# power-supply.net
KiCad netlist of a schematic drawn in Altium Designer
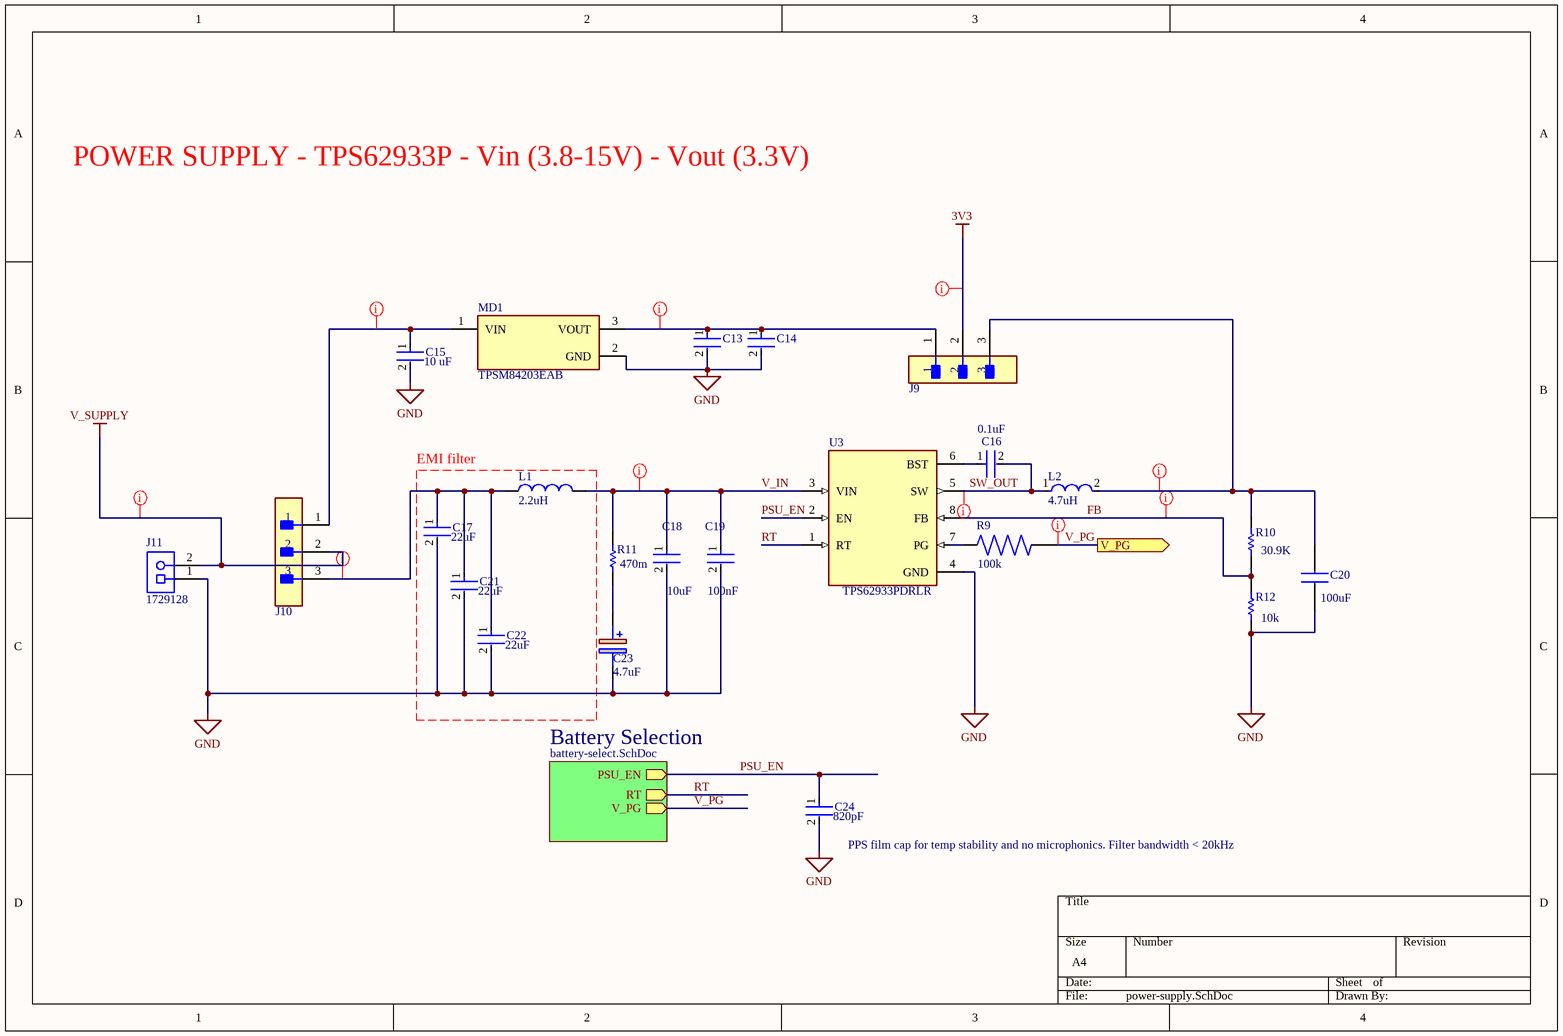
[diagram p0: power-supply.SchDoc]

(export (version "E")
  (design (tool "Eeschema 10.0.6"))
  (components
    (comp (ref "C13")
      (value "~")
      (footprint "FP-C3216-160-0_2-MFG")
      (description "Multilayer Ceramic Capacitors 47uF ±20% 25V X5R SMD 1206")
      (fields (field (name "VOLTAGE") "25V") (field (name "TOLERANCE") "20%"))
      (libsource (lib "FLoRa0.0") (part "11868f565c42a9108669ba33697ecf6"))
    )
    (comp (ref "C14")
      (value "~")
      (footprint "FP-C3216-160-0_2-MFG")
      (description "Multilayer Ceramic Capacitors 47uF ±20% 25V X5R SMD 1206")
      (fields (field (name "VOLTAGE") "25V") (field (name "TOLERANCE") "20%"))
      (libsource (lib "FLoRa0.0") (part "11868f565c42a9108669ba33697ecf6"))
    )
    (comp (ref "C15")
      (value "10 uF")
      (footprint "FP-GRT31C-0_2-IPC_A")
      (description "Multi-Layer Ceramic Capacitor 10uF 50V X5R ±10% 1206 Emboss T/R")
      (fields (field (name "TOLERANCE") "10%"))
      (libsource (lib "Altium Content Vault") (part "02cd4be3c70576c341d710602a673aa"))
    )
    (comp (ref "C16")
      (value "0.1uF")
      (footprint "FP-C0603C104Z4VACTU-MFG")
      (description "CAP CER 0.1UF 16V Y5V 0603")
      (fields (field (name "TOLERANCE") "80%"))
      (libsource (lib "Altium Content Vault") (part "b4654b650e69147ec39a6b967a45e02"))
    )
    (comp (ref "C17")
      (value "22uF")
      (footprint "FP-GRM32-MFG")
      (description "CAP CER 22UF 25V X5R 1210")
      (fields
        (field (name "TOLERANCE") "10%")
        (field (name "MANUFACTURER") "Murata Electronics North America")
      )
      (libsource (lib "Altium Content Vault") (part "11868f565c42a9108669ba33697ecf6"))
    )
    (comp (ref "C18")
      (value "10uF")
      (footprint "FP-GRM21B-0_15-IPC_A")
      (description "Chip Multilayer Ceramic Capacitors for General Purpose, 0805, 10uF, X5R, 15%, 20%, 25V")
      (fields (field (name "TOLERANCE") "20%"))
      (libsource (lib "Altium Content Vault") (part "b4654b650e69147ec39a6b967a45e02"))
    )
    (comp (ref "C19")
      (value "100nF")
      (footprint "FP-0603-L_1_6_0_15-W_0_81-MFG")
      (description "General Purpose Ceramic Capacitor, 0603, 100nF, 10%, X7R, 15%, 25V")
      (fields (field (name "VOLTAGE") "25V") (field (name "TOLERANCE") "10%"))
      (libsource (lib "Altium Content Vault") (part "02cd4be3c70576c341d710602a673aa"))
    )
    (comp (ref "C20")
      (value "100uF")
      (footprint "CAPC3225X270N")
      (fields
        (field (name "MOUSER PART NUMBER") "81-GRM32EC80J107ME0L")
        (field (name "MANUFACTURER_PART_NUMBER") "GRM32EC80J107ME20L")
      )
      (libsource (lib "GRM32EC80J107ME20L") (part "GRM32EC80J107ME20L"))
    )
    (comp (ref "C21")
      (value "22uF")
      (footprint "FP-GRM32-MFG")
      (description "CAP CER 22UF 25V X5R 1210")
      (fields
        (field (name "TOLERANCE") "10%")
        (field (name "MANUFACTURER") "Murata Electronics North America")
      )
      (libsource (lib "Altium Content Vault") (part "11868f565c42a9108669ba33697ecf6"))
    )
    (comp (ref "C22")
      (value "22uF")
      (footprint "FP-GRM32-MFG")
      (description "CAP CER 22UF 25V X5R 1210")
      (fields
        (field (name "TOLERANCE") "10%")
        (field (name "MANUFACTURER") "Murata Electronics North America")
      )
      (libsource (lib "Altium Content Vault") (part "11868f565c42a9108669ba33697ecf6"))
    )
    (comp (ref "C23")
      (value "4.7uF")
      (footprint "CAPPM3528X120N")
      (description "Cap Tant Solid 4.7uF 35V B CASE 10% (3.5 X 2.8 X 1.9mm) Inward L SMD 3528-21 0.7 Ohm 125C T/R")
      (fields
        (field (name "MOUSER PART NUMBER") "581-TPSB475K035R0700")
        (field (name "MANUFACTURER_PART_NUMBER") "TPSB475K035R0700")
      )
      (libsource (lib "TPSB475K035R0700") (part "TPSB475K035R0700"))
    )
    (comp (ref "C24")
      (value "ECH-U1H821JX5")
      (footprint "FP-ECHUJ1-MFG")
      (description "CAP FILM 820PF 5% 50VDC 0805")
      (fields
        (field (name "TOLERANCE") "5%")
        (field (name "CAPACITANCE") "820pF")
        (field (name "VOLTAGE") "50V")
      )
      (libsource (lib "Altium Content Vault") (part "b4654b650e69147ec39a6b967a45e02"))
    )
    (comp (ref "J9")
      (value "PREC003SAAN-RC")
      (footprint "FP-PREC003SAAN-RC-MFG")
      (description "PREC003SAAN-RC Conn Header Vert 3POS 2.54MM")
      (libsource (lib "Altium Content Vault") (part "0d3f023dd272f625e17a2be33dea85f"))
    )
    (comp (ref "J10")
      (value "3POS_MALECONN-2.54mm")
      (footprint "FLoRa0.02:SIP3-100mil")
      (description "Vertical male 3 position connector 2.54mm pitch")
      (libsource (lib "FLoRa0.0") (part "3POS_MALECONN-2.54mm"))
    )
    (comp (ref "J11")
      (value "1729128")
      (footprint "FLoRa0.02:PHOE-1729128-2_V")
      (description "PCB Terminal Block, 13.5 A, 400 V, 2-Pin THD, RoHS, Bulk")
      (fields (field (name "MANUFACTURER") "Phoenix Contact"))
      (libsource (lib "FLoRa0.0") (part "CMP-2000-05815-1"))
    )
    (comp (ref "L1")
      (value "2.2uH")
      (footprint "WE-PMCI_1210_L3.2W2.5H1.2")
      (description "74479299222 General Purpose Inductor, 2.2uH, 15%, 1 Element, Iron Alloy-Core, SMD, 1210")
      (fields (field (name "TOLERANCE") "20%"))
      (libsource (lib "Altium Content Vault") (part "Inductor - 1"))
    )
    (comp (ref "L2")
      (value "4.7uH")
      (footprint "FP-IHLP-3232DZ-FP_2_413x5-MFG")
      (description "Commercial Inductors, Low DCR Series 4.7uH 8A 22.6mΩ 20%")
      (fields (field (name "TOLERANCE") "20%"))
      (libsource (lib "Altium Content Vault") (part "725321dda6339637d4d059423bc1c3c"))
    )
    (comp (ref "MD1")
      (value "TPSM84203EAB")
      (footprint "FLoRa0.02:FP-EAB0003A-MFG")
      (description "Switching Regulator, Current-mode, 1.5A, 510kHz Switching Freq-Max, Hybrid")
      (fields (field (name "MANUFACTURER") "Texas Instruments"))
      (libsource (lib "FLoRa0.0") (part "TPS_EVAL_BOARD"))
    )
    (comp (ref "R9")
      (value "100k")
      (footprint "RESC1508X50N")
      (fields (field (name "MF") "Vishay") (field (name "MP") "CRCW0603100KFKEA"))
      (libsource (lib "CRCW0603100KFKEA") (part "CRCW0603100KFKEA"))
    )
    (comp (ref "R10")
      (value "30.9K")
      (footprint "RESC1608X55X25NL10T15")
      (description "Rfbt")
      (fields (field (name "MANUFACTURER") "Yageo") (field (name "PART NUMBER") "RC0603FR-0730K9L"))
      (libsource (lib "Altium Content Vault") (part "RES"))
    )
    (comp (ref "R11")
      (value "470m")
      (footprint "RESC2013X70X40NL20T20")
      (fields (field (name "MANUFACTURER") "Panasonic") (field (name "PART NUMBER") "ERJ-6RQFR47V"))
      (libsource (lib "Altium Content Vault") (part "RES"))
    )
    (comp (ref "R12")
      (value "10k")
      (footprint "RESC1609X50X30NL8T20")
      (fields (field (name "MANUFACTURER") "Vishay Semiconductor"))
      (libsource (lib "Altium Content Vault") (part "RES-2"))
    )
    (comp (ref "U3")
      (value "TPS62933PDRLR")
      (footprint "SOFL50P160X60-8S")
      (libsource (lib "TPS62933PDRLR") (part "TPS62933PDRLR"))
    )
  )
  (nets
    (net (code "1") (name "/FB") (class "Default")
      (node (ref "R10") (pin "1") (pinfunction "1_1") (pintype "passive"))
      (node (ref "R12") (pin "2") (pinfunction "2_2") (pintype "passive"))
      (node (ref "U3") (pin "8") (pinfunction "FB_8") (pintype "input"))
    )
    (net (code "2") (name "/PSU_EN") (class "Default")
      (node (ref "C24") (pin "1") (pinfunction "1_1") (pintype "passive"))
      (node (ref "U3") (pin "2") (pinfunction "EN_2") (pintype "input"))
    )
    (net (code "3") (name "/RT") (class "Default")
      (node (ref "U3") (pin "1") (pinfunction "RT_1") (pintype "input"))
    )
    (net (code "4") (name "/SW_OUT") (class "Default")
      (node (ref "C16") (pin "2") (pinfunction "2_2") (pintype "passive"))
      (node (ref "L2") (pin "1") (pinfunction "1_1") (pintype "passive"))
      (node (ref "U3") (pin "5") (pinfunction "SW_5") (pintype "output"))
    )
    (net (code "5") (name "/V_IN") (class "Default")
      (node (ref "C18") (pin "1") (pinfunction "1_1") (pintype "passive"))
      (node (ref "C19") (pin "1") (pinfunction "1_1") (pintype "passive"))
      (node (ref "L1") (pin "2") (pinfunction "2_2") (pintype "passive"))
      (node (ref "R11") (pin "2") (pinfunction "2_2") (pintype "passive"))
      (node (ref "U3") (pin "3") (pinfunction "VIN_3") (pintype "input"))
    )
    (net (code "6") (name "/V_PG") (class "Default")
      (node (ref "R9") (pin "2") (pinfunction "2_2") (pintype "passive"))
    )
    (net (code "7") (name "3V3") (class "Default")
      (node (ref "J9") (pin "2") (pinfunction "2_2") (pintype "passive"))
    )
    (net (code "8") (name "GND") (class "Default")
      (node (ref "C13") (pin "2") (pinfunction "2_2") (pintype "passive"))
      (node (ref "C14") (pin "2") (pinfunction "2_2") (pintype "passive"))
      (node (ref "C15") (pin "2") (pinfunction "2_2") (pintype "passive"))
      (node (ref "C17") (pin "2") (pinfunction "2_2") (pintype "passive"))
      (node (ref "C18") (pin "2") (pinfunction "2_2") (pintype "passive"))
      (node (ref "C19") (pin "2") (pinfunction "2_2") (pintype "passive"))
      (node (ref "C20") (pin "1") (pinfunction "1_1") (pintype "passive"))
      (node (ref "C21") (pin "2") (pinfunction "2_2") (pintype "passive"))
      (node (ref "C22") (pin "2") (pinfunction "2_2") (pintype "passive"))
      (node (ref "C23") (pin "2") (pinfunction "-_2") (pintype "passive"))
      (node (ref "C24") (pin "2") (pinfunction "2_2") (pintype "passive"))
      (node (ref "J11") (pin "1") (pinfunction "1_1") (pintype "passive"))
      (node (ref "MD1") (pin "2") (pinfunction "GND_2") (pintype "power_in"))
      (node (ref "R12") (pin "1") (pinfunction "1_1") (pintype "passive"))
      (node (ref "U3") (pin "4") (pinfunction "GND_4") (pintype "power_in"))
    )
    (net (code "9") (name "Net-(C17-Pad1)") (class "Default")
      (node (ref "C17") (pin "1") (pinfunction "1_1") (pintype "passive"))
      (node (ref "C21") (pin "1") (pinfunction "1_1") (pintype "passive"))
      (node (ref "C22") (pin "1") (pinfunction "1_1") (pintype "passive"))
      (node (ref "J10") (pin "3") (pinfunction "3_3") (pintype "passive"))
      (node (ref "L1") (pin "1") (pinfunction "1_1") (pintype "passive"))
    )
    (net (code "10") (name "Net-(C20-Pad2)") (class "Default")
      (node (ref "C20") (pin "2") (pinfunction "2_2") (pintype "passive"))
      (node (ref "J9") (pin "3") (pinfunction "3_3") (pintype "passive"))
      (node (ref "L2") (pin "2") (pinfunction "2_2") (pintype "passive"))
      (node (ref "R10") (pin "2") (pinfunction "2_2") (pintype "passive"))
    )
    (net (code "11") (name "Net-(C23-+)") (class "Default")
      (node (ref "C23") (pin "1") (pinfunction "+_1") (pintype "passive"))
      (node (ref "R11") (pin "1") (pinfunction "1_1") (pintype "passive"))
    )
    (net (code "12") (name "Net-(MD1-VIN)") (class "Default")
      (node (ref "C15") (pin "1") (pinfunction "1_1") (pintype "passive"))
      (node (ref "J10") (pin "1") (pinfunction "1_1") (pintype "passive"))
      (node (ref "MD1") (pin "1") (pinfunction "VIN_1") (pintype "power_in"))
    )
    (net (code "13") (name "Net-(MD1-VOUT)") (class "Default")
      (node (ref "C13") (pin "1") (pinfunction "1_1") (pintype "passive"))
      (node (ref "C14") (pin "1") (pinfunction "1_1") (pintype "passive"))
      (node (ref "J9") (pin "1") (pinfunction "1_1") (pintype "passive"))
      (node (ref "MD1") (pin "3") (pinfunction "VOUT_3") (pintype "power_in"))
    )
    (net (code "14") (name "Net-(U3-BST)") (class "Default")
      (node (ref "C16") (pin "1") (pinfunction "1_1") (pintype "passive"))
      (node (ref "U3") (pin "6") (pinfunction "BST_6") (pintype "power_in"))
    )
    (net (code "15") (name "Net-(U3-PG)") (class "Default")
      (node (ref "R9") (pin "1") (pinfunction "1_1") (pintype "passive"))
      (node (ref "U3") (pin "7") (pinfunction "PG_7") (pintype "input"))
    )
    (net (code "16") (name "V_SUPPLY") (class "Default")
      (node (ref "J10") (pin "2") (pinfunction "2_2") (pintype "passive"))
      (node (ref "J11") (pin "2") (pinfunction "2_2") (pintype "passive"))
    )
  )
)
